# untitled.net
KiCad netlist of a schematic drawn in EAGLE
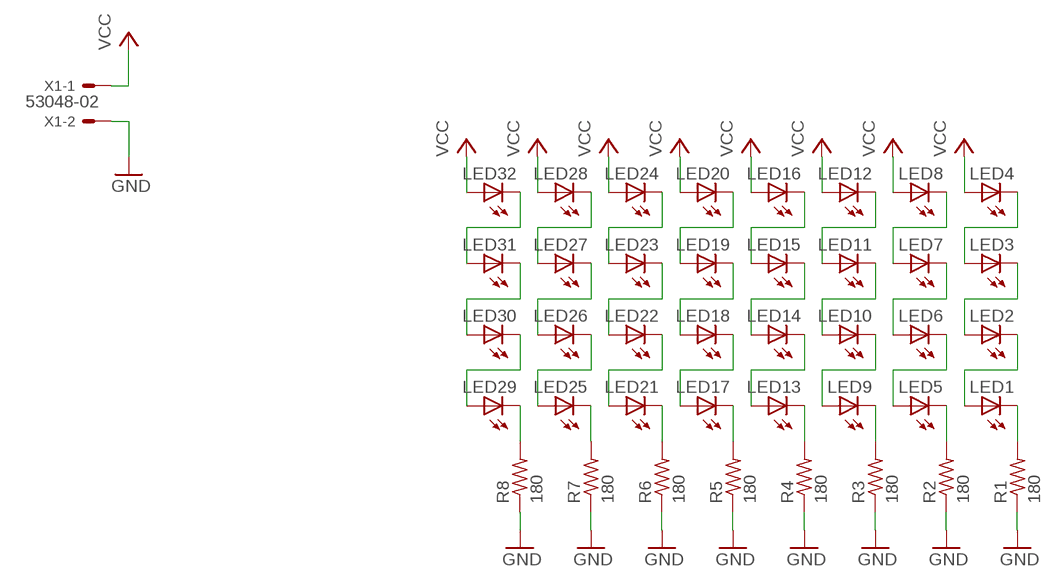
[diagram p0: schematic, sheet 1]

(export (version "E")
  (design (tool "Eeschema 10.0.6"))
  (components
    (comp (ref "LED1")
      (value "LED5MM")
      (footprint "eagle-import:LED5MM")
      (fields (field (name "MPN") "C503B-RCN-CW0Z0AA1"))
      (libsource (lib "eagle-import") (part "LED5MM"))
    )
    (comp (ref "LED2")
      (value "LED5MM")
      (footprint "eagle-import:LED5MM")
      (fields (field (name "MPN") "C503B-RCN-CW0Z0AA1"))
      (libsource (lib "eagle-import") (part "LED5MM"))
    )
    (comp (ref "LED3")
      (value "LED5MM")
      (footprint "eagle-import:LED5MM")
      (fields (field (name "MPN") "C503B-RCN-CW0Z0AA1"))
      (libsource (lib "eagle-import") (part "LED5MM"))
    )
    (comp (ref "LED4")
      (value "LED5MM")
      (footprint "eagle-import:LED5MM")
      (fields (field (name "MPN") "C503B-RCN-CW0Z0AA1"))
      (libsource (lib "eagle-import") (part "LED5MM"))
    )
    (comp (ref "LED5")
      (value "LED5MM")
      (footprint "eagle-import:LED5MM")
      (fields (field (name "MPN") "C503B-RCN-CW0Z0AA1"))
      (libsource (lib "eagle-import") (part "LED5MM"))
    )
    (comp (ref "LED6")
      (value "LED5MM")
      (footprint "eagle-import:LED5MM")
      (fields (field (name "MPN") "C503B-RCN-CW0Z0AA1"))
      (libsource (lib "eagle-import") (part "LED5MM"))
    )
    (comp (ref "LED7")
      (value "LED5MM")
      (footprint "eagle-import:LED5MM")
      (fields (field (name "MPN") "C503B-RCN-CW0Z0AA1"))
      (libsource (lib "eagle-import") (part "LED5MM"))
    )
    (comp (ref "LED8")
      (value "LED5MM")
      (footprint "eagle-import:LED5MM")
      (fields (field (name "MPN") "C503B-RCN-CW0Z0AA1"))
      (libsource (lib "eagle-import") (part "LED5MM"))
    )
    (comp (ref "LED9")
      (value "LED5MM")
      (footprint "eagle-import:LED5MM")
      (fields (field (name "MPN") "C503B-RCN-CW0Z0AA1"))
      (libsource (lib "eagle-import") (part "LED5MM"))
    )
    (comp (ref "LED10")
      (value "LED5MM")
      (footprint "eagle-import:LED5MM")
      (fields (field (name "MPN") "C503B-RCN-CW0Z0AA1"))
      (libsource (lib "eagle-import") (part "LED5MM"))
    )
    (comp (ref "LED11")
      (value "LED5MM")
      (footprint "eagle-import:LED5MM")
      (fields (field (name "MPN") "C503B-RCN-CW0Z0AA1"))
      (libsource (lib "eagle-import") (part "LED5MM"))
    )
    (comp (ref "LED12")
      (value "LED5MM")
      (footprint "eagle-import:LED5MM")
      (fields (field (name "MPN") "C503B-RCN-CW0Z0AA1"))
      (libsource (lib "eagle-import") (part "LED5MM"))
    )
    (comp (ref "LED13")
      (value "LED5MM")
      (footprint "eagle-import:LED5MM")
      (fields (field (name "MPN") "C503B-RCN-CW0Z0AA1"))
      (libsource (lib "eagle-import") (part "LED5MM"))
    )
    (comp (ref "LED14")
      (value "LED5MM")
      (footprint "eagle-import:LED5MM")
      (fields (field (name "MPN") "C503B-RCN-CW0Z0AA1"))
      (libsource (lib "eagle-import") (part "LED5MM"))
    )
    (comp (ref "LED15")
      (value "LED5MM")
      (footprint "eagle-import:LED5MM")
      (fields (field (name "MPN") "C503B-RCN-CW0Z0AA1"))
      (libsource (lib "eagle-import") (part "LED5MM"))
    )
    (comp (ref "LED16")
      (value "LED5MM")
      (footprint "eagle-import:LED5MM")
      (fields (field (name "MPN") "C503B-RCN-CW0Z0AA1"))
      (libsource (lib "eagle-import") (part "LED5MM"))
    )
    (comp (ref "LED17")
      (value "LED5MM")
      (footprint "eagle-import:LED5MM")
      (fields (field (name "MPN") "C503B-RCN-CW0Z0AA1"))
      (libsource (lib "eagle-import") (part "LED5MM"))
    )
    (comp (ref "LED18")
      (value "LED5MM")
      (footprint "eagle-import:LED5MM")
      (fields (field (name "MPN") "C503B-RCN-CW0Z0AA1"))
      (libsource (lib "eagle-import") (part "LED5MM"))
    )
    (comp (ref "LED19")
      (value "LED5MM")
      (footprint "eagle-import:LED5MM")
      (fields (field (name "MPN") "C503B-RCN-CW0Z0AA1"))
      (libsource (lib "eagle-import") (part "LED5MM"))
    )
    (comp (ref "LED20")
      (value "LED5MM")
      (footprint "eagle-import:LED5MM")
      (fields (field (name "MPN") "C503B-RCN-CW0Z0AA1"))
      (libsource (lib "eagle-import") (part "LED5MM"))
    )
    (comp (ref "LED21")
      (value "LED5MM")
      (footprint "eagle-import:LED5MM")
      (fields (field (name "MPN") "C503B-RCN-CW0Z0AA1"))
      (libsource (lib "eagle-import") (part "LED5MM"))
    )
    (comp (ref "LED22")
      (value "LED5MM")
      (footprint "eagle-import:LED5MM")
      (fields (field (name "MPN") "C503B-RCN-CW0Z0AA1"))
      (libsource (lib "eagle-import") (part "LED5MM"))
    )
    (comp (ref "LED23")
      (value "LED5MM")
      (footprint "eagle-import:LED5MM")
      (fields (field (name "MPN") "C503B-RCN-CW0Z0AA1"))
      (libsource (lib "eagle-import") (part "LED5MM"))
    )
    (comp (ref "LED24")
      (value "LED5MM")
      (footprint "eagle-import:LED5MM")
      (fields (field (name "MPN") "C503B-RCN-CW0Z0AA1"))
      (libsource (lib "eagle-import") (part "LED5MM"))
    )
    (comp (ref "LED25")
      (value "LED5MM")
      (footprint "eagle-import:LED5MM")
      (fields (field (name "MPN") "C503B-RCN-CW0Z0AA1"))
      (libsource (lib "eagle-import") (part "LED5MM"))
    )
    (comp (ref "LED26")
      (value "LED5MM")
      (footprint "eagle-import:LED5MM")
      (fields (field (name "MPN") "C503B-RCN-CW0Z0AA1"))
      (libsource (lib "eagle-import") (part "LED5MM"))
    )
    (comp (ref "LED27")
      (value "LED5MM")
      (footprint "eagle-import:LED5MM")
      (fields (field (name "MPN") "C503B-RCN-CW0Z0AA1"))
      (libsource (lib "eagle-import") (part "LED5MM"))
    )
    (comp (ref "LED28")
      (value "LED5MM")
      (footprint "eagle-import:LED5MM")
      (fields (field (name "MPN") "C503B-RCN-CW0Z0AA1"))
      (libsource (lib "eagle-import") (part "LED5MM"))
    )
    (comp (ref "LED29")
      (value "LED5MM")
      (footprint "eagle-import:LED5MM")
      (fields (field (name "MPN") "C503B-RCN-CW0Z0AA1"))
      (libsource (lib "eagle-import") (part "LED5MM"))
    )
    (comp (ref "LED30")
      (value "LED5MM")
      (footprint "eagle-import:LED5MM")
      (fields (field (name "MPN") "C503B-RCN-CW0Z0AA1"))
      (libsource (lib "eagle-import") (part "LED5MM"))
    )
    (comp (ref "LED31")
      (value "LED5MM")
      (footprint "eagle-import:LED5MM")
      (fields (field (name "MPN") "C503B-RCN-CW0Z0AA1"))
      (libsource (lib "eagle-import") (part "LED5MM"))
    )
    (comp (ref "LED32")
      (value "LED5MM")
      (footprint "eagle-import:LED5MM")
      (fields (field (name "MPN") "C503B-RCN-CW0Z0AA1"))
      (libsource (lib "eagle-import") (part "LED5MM"))
    )
    (comp (ref "R1")
      (value "180")
      (footprint "eagle-import:0207_10")
      (fields (field (name "MF") "FARNELL") (field (name "MPN") "MCF 0.25W 180R"))
      (libsource (lib "eagle-import") (part "R-US_0207/10"))
    )
    (comp (ref "R2")
      (value "180")
      (footprint "eagle-import:0207_10")
      (fields (field (name "MF") "FARNELL") (field (name "MPN") "MCF 0.25W 180R"))
      (libsource (lib "eagle-import") (part "R-US_0207/10"))
    )
    (comp (ref "R3")
      (value "180")
      (footprint "eagle-import:0207_10")
      (fields (field (name "MF") "FARNELL") (field (name "MPN") "MCF 0.25W 180R"))
      (libsource (lib "eagle-import") (part "R-US_0207/10"))
    )
    (comp (ref "R4")
      (value "180")
      (footprint "eagle-import:0207_10")
      (fields (field (name "MF") "FARNELL") (field (name "MPN") "MCF 0.25W 180R"))
      (libsource (lib "eagle-import") (part "R-US_0207/10"))
    )
    (comp (ref "R5")
      (value "180")
      (footprint "eagle-import:0207_10")
      (fields (field (name "MF") "FARNELL") (field (name "MPN") "MCF 0.25W 180R"))
      (libsource (lib "eagle-import") (part "R-US_0207/10"))
    )
    (comp (ref "R6")
      (value "180")
      (footprint "eagle-import:0207_10")
      (fields (field (name "MF") "FARNELL") (field (name "MPN") "MCF 0.25W 180R"))
      (libsource (lib "eagle-import") (part "R-US_0207/10"))
    )
    (comp (ref "R7")
      (value "180")
      (footprint "eagle-import:0207_10")
      (fields (field (name "MF") "FARNELL") (field (name "MPN") "MCF 0.25W 180R"))
      (libsource (lib "eagle-import") (part "R-US_0207/10"))
    )
    (comp (ref "R8")
      (value "180")
      (footprint "eagle-import:0207_10")
      (fields (field (name "MF") "FARNELL") (field (name "MPN") "MCF 0.25W 180R"))
      (libsource (lib "eagle-import") (part "R-US_0207/10"))
    )
    (comp (ref "X1")
      (value "53048-02")
      (footprint "eagle-import:53048-02")
      (fields (field (name "MF") "MOLEX") (field (name "MPN") "53048-0210"))
      (libsource (lib "eagle-import") (part "53?-02048"))
    )
  )
  (nets
    (net (code "1") (name "GND") (class "Default")
      (node (ref "R1") (pin "1") (pinfunction "1_1") (pintype "passive"))
      (node (ref "R2") (pin "1") (pinfunction "1_1") (pintype "passive"))
      (node (ref "R3") (pin "1") (pinfunction "1_1") (pintype "passive"))
      (node (ref "R4") (pin "1") (pinfunction "1_1") (pintype "passive"))
      (node (ref "R5") (pin "1") (pinfunction "1_1") (pintype "passive"))
      (node (ref "R6") (pin "1") (pinfunction "1_1") (pintype "passive"))
      (node (ref "R7") (pin "1") (pinfunction "1_1") (pintype "passive"))
      (node (ref "R8") (pin "1") (pinfunction "1_1") (pintype "passive"))
      (node (ref "X1") (pin "2") (pinfunction "S_2") (pintype "passive"))
    )
    (net (code "2") (name "Net-(LED1-C)") (class "Default")
      (node (ref "LED1") (pin "K") (pinfunction "C_K") (pintype "passive"))
      (node (ref "R1") (pin "2") (pinfunction "2_2") (pintype "passive"))
    )
    (net (code "3") (name "Net-(LED2-C)") (class "Default")
      (node (ref "LED1") (pin "A") (pinfunction "A_A") (pintype "passive"))
      (node (ref "LED2") (pin "K") (pinfunction "C_K") (pintype "passive"))
    )
    (net (code "4") (name "Net-(LED3-C)") (class "Default")
      (node (ref "LED2") (pin "A") (pinfunction "A_A") (pintype "passive"))
      (node (ref "LED3") (pin "K") (pinfunction "C_K") (pintype "passive"))
    )
    (net (code "5") (name "Net-(LED4-C)") (class "Default")
      (node (ref "LED3") (pin "A") (pinfunction "A_A") (pintype "passive"))
      (node (ref "LED4") (pin "K") (pinfunction "C_K") (pintype "passive"))
    )
    (net (code "6") (name "Net-(LED5-C)") (class "Default")
      (node (ref "LED5") (pin "K") (pinfunction "C_K") (pintype "passive"))
      (node (ref "R2") (pin "2") (pinfunction "2_2") (pintype "passive"))
    )
    (net (code "7") (name "Net-(LED6-C)") (class "Default")
      (node (ref "LED5") (pin "A") (pinfunction "A_A") (pintype "passive"))
      (node (ref "LED6") (pin "K") (pinfunction "C_K") (pintype "passive"))
    )
    (net (code "8") (name "Net-(LED7-C)") (class "Default")
      (node (ref "LED6") (pin "A") (pinfunction "A_A") (pintype "passive"))
      (node (ref "LED7") (pin "K") (pinfunction "C_K") (pintype "passive"))
    )
    (net (code "9") (name "Net-(LED8-C)") (class "Default")
      (node (ref "LED7") (pin "A") (pinfunction "A_A") (pintype "passive"))
      (node (ref "LED8") (pin "K") (pinfunction "C_K") (pintype "passive"))
    )
    (net (code "10") (name "Net-(LED9-C)") (class "Default")
      (node (ref "LED9") (pin "K") (pinfunction "C_K") (pintype "passive"))
      (node (ref "R3") (pin "2") (pinfunction "2_2") (pintype "passive"))
    )
    (net (code "11") (name "Net-(LED10-C)") (class "Default")
      (node (ref "LED10") (pin "K") (pinfunction "C_K") (pintype "passive"))
      (node (ref "LED9") (pin "A") (pinfunction "A_A") (pintype "passive"))
    )
    (net (code "12") (name "Net-(LED11-C)") (class "Default")
      (node (ref "LED10") (pin "A") (pinfunction "A_A") (pintype "passive"))
      (node (ref "LED11") (pin "K") (pinfunction "C_K") (pintype "passive"))
    )
    (net (code "13") (name "Net-(LED12-C)") (class "Default")
      (node (ref "LED11") (pin "A") (pinfunction "A_A") (pintype "passive"))
      (node (ref "LED12") (pin "K") (pinfunction "C_K") (pintype "passive"))
    )
    (net (code "14") (name "Net-(LED13-C)") (class "Default")
      (node (ref "LED13") (pin "K") (pinfunction "C_K") (pintype "passive"))
      (node (ref "R4") (pin "2") (pinfunction "2_2") (pintype "passive"))
    )
    (net (code "15") (name "Net-(LED14-C)") (class "Default")
      (node (ref "LED13") (pin "A") (pinfunction "A_A") (pintype "passive"))
      (node (ref "LED14") (pin "K") (pinfunction "C_K") (pintype "passive"))
    )
    (net (code "16") (name "Net-(LED15-C)") (class "Default")
      (node (ref "LED14") (pin "A") (pinfunction "A_A") (pintype "passive"))
      (node (ref "LED15") (pin "K") (pinfunction "C_K") (pintype "passive"))
    )
    (net (code "17") (name "Net-(LED16-C)") (class "Default")
      (node (ref "LED15") (pin "A") (pinfunction "A_A") (pintype "passive"))
      (node (ref "LED16") (pin "K") (pinfunction "C_K") (pintype "passive"))
    )
    (net (code "18") (name "Net-(LED17-C)") (class "Default")
      (node (ref "LED17") (pin "K") (pinfunction "C_K") (pintype "passive"))
      (node (ref "R5") (pin "2") (pinfunction "2_2") (pintype "passive"))
    )
    (net (code "19") (name "Net-(LED18-C)") (class "Default")
      (node (ref "LED17") (pin "A") (pinfunction "A_A") (pintype "passive"))
      (node (ref "LED18") (pin "K") (pinfunction "C_K") (pintype "passive"))
    )
    (net (code "20") (name "Net-(LED19-C)") (class "Default")
      (node (ref "LED18") (pin "A") (pinfunction "A_A") (pintype "passive"))
      (node (ref "LED19") (pin "K") (pinfunction "C_K") (pintype "passive"))
    )
    (net (code "21") (name "Net-(LED20-C)") (class "Default")
      (node (ref "LED19") (pin "A") (pinfunction "A_A") (pintype "passive"))
      (node (ref "LED20") (pin "K") (pinfunction "C_K") (pintype "passive"))
    )
    (net (code "22") (name "Net-(LED21-C)") (class "Default")
      (node (ref "LED21") (pin "K") (pinfunction "C_K") (pintype "passive"))
      (node (ref "R6") (pin "2") (pinfunction "2_2") (pintype "passive"))
    )
    (net (code "23") (name "Net-(LED22-C)") (class "Default")
      (node (ref "LED21") (pin "A") (pinfunction "A_A") (pintype "passive"))
      (node (ref "LED22") (pin "K") (pinfunction "C_K") (pintype "passive"))
    )
    (net (code "24") (name "Net-(LED23-C)") (class "Default")
      (node (ref "LED22") (pin "A") (pinfunction "A_A") (pintype "passive"))
      (node (ref "LED23") (pin "K") (pinfunction "C_K") (pintype "passive"))
    )
    (net (code "25") (name "Net-(LED24-C)") (class "Default")
      (node (ref "LED23") (pin "A") (pinfunction "A_A") (pintype "passive"))
      (node (ref "LED24") (pin "K") (pinfunction "C_K") (pintype "passive"))
    )
    (net (code "26") (name "Net-(LED25-C)") (class "Default")
      (node (ref "LED25") (pin "K") (pinfunction "C_K") (pintype "passive"))
      (node (ref "R7") (pin "2") (pinfunction "2_2") (pintype "passive"))
    )
    (net (code "27") (name "Net-(LED26-C)") (class "Default")
      (node (ref "LED25") (pin "A") (pinfunction "A_A") (pintype "passive"))
      (node (ref "LED26") (pin "K") (pinfunction "C_K") (pintype "passive"))
    )
    (net (code "28") (name "Net-(LED27-C)") (class "Default")
      (node (ref "LED26") (pin "A") (pinfunction "A_A") (pintype "passive"))
      (node (ref "LED27") (pin "K") (pinfunction "C_K") (pintype "passive"))
    )
    (net (code "29") (name "Net-(LED28-C)") (class "Default")
      (node (ref "LED27") (pin "A") (pinfunction "A_A") (pintype "passive"))
      (node (ref "LED28") (pin "K") (pinfunction "C_K") (pintype "passive"))
    )
    (net (code "30") (name "Net-(LED29-C)") (class "Default")
      (node (ref "LED29") (pin "K") (pinfunction "C_K") (pintype "passive"))
      (node (ref "R8") (pin "2") (pinfunction "2_2") (pintype "passive"))
    )
    (net (code "31") (name "Net-(LED30-C)") (class "Default")
      (node (ref "LED29") (pin "A") (pinfunction "A_A") (pintype "passive"))
      (node (ref "LED30") (pin "K") (pinfunction "C_K") (pintype "passive"))
    )
    (net (code "32") (name "Net-(LED31-C)") (class "Default")
      (node (ref "LED30") (pin "A") (pinfunction "A_A") (pintype "passive"))
      (node (ref "LED31") (pin "K") (pinfunction "C_K") (pintype "passive"))
    )
    (net (code "33") (name "Net-(LED32-C)") (class "Default")
      (node (ref "LED31") (pin "A") (pinfunction "A_A") (pintype "passive"))
      (node (ref "LED32") (pin "K") (pinfunction "C_K") (pintype "passive"))
    )
    (net (code "34") (name "VCC") (class "Default")
      (node (ref "LED12") (pin "A") (pinfunction "A_A") (pintype "passive"))
      (node (ref "LED16") (pin "A") (pinfunction "A_A") (pintype "passive"))
      (node (ref "LED20") (pin "A") (pinfunction "A_A") (pintype "passive"))
      (node (ref "LED24") (pin "A") (pinfunction "A_A") (pintype "passive"))
      (node (ref "LED28") (pin "A") (pinfunction "A_A") (pintype "passive"))
      (node (ref "LED32") (pin "A") (pinfunction "A_A") (pintype "passive"))
      (node (ref "LED4") (pin "A") (pinfunction "A_A") (pintype "passive"))
      (node (ref "LED8") (pin "A") (pinfunction "A_A") (pintype "passive"))
      (node (ref "X1") (pin "1") (pinfunction "S_1") (pintype "passive"))
    )
  )
)
